# SMART3RGB.net
KiCad netlist of a schematic drawn in EAGLE
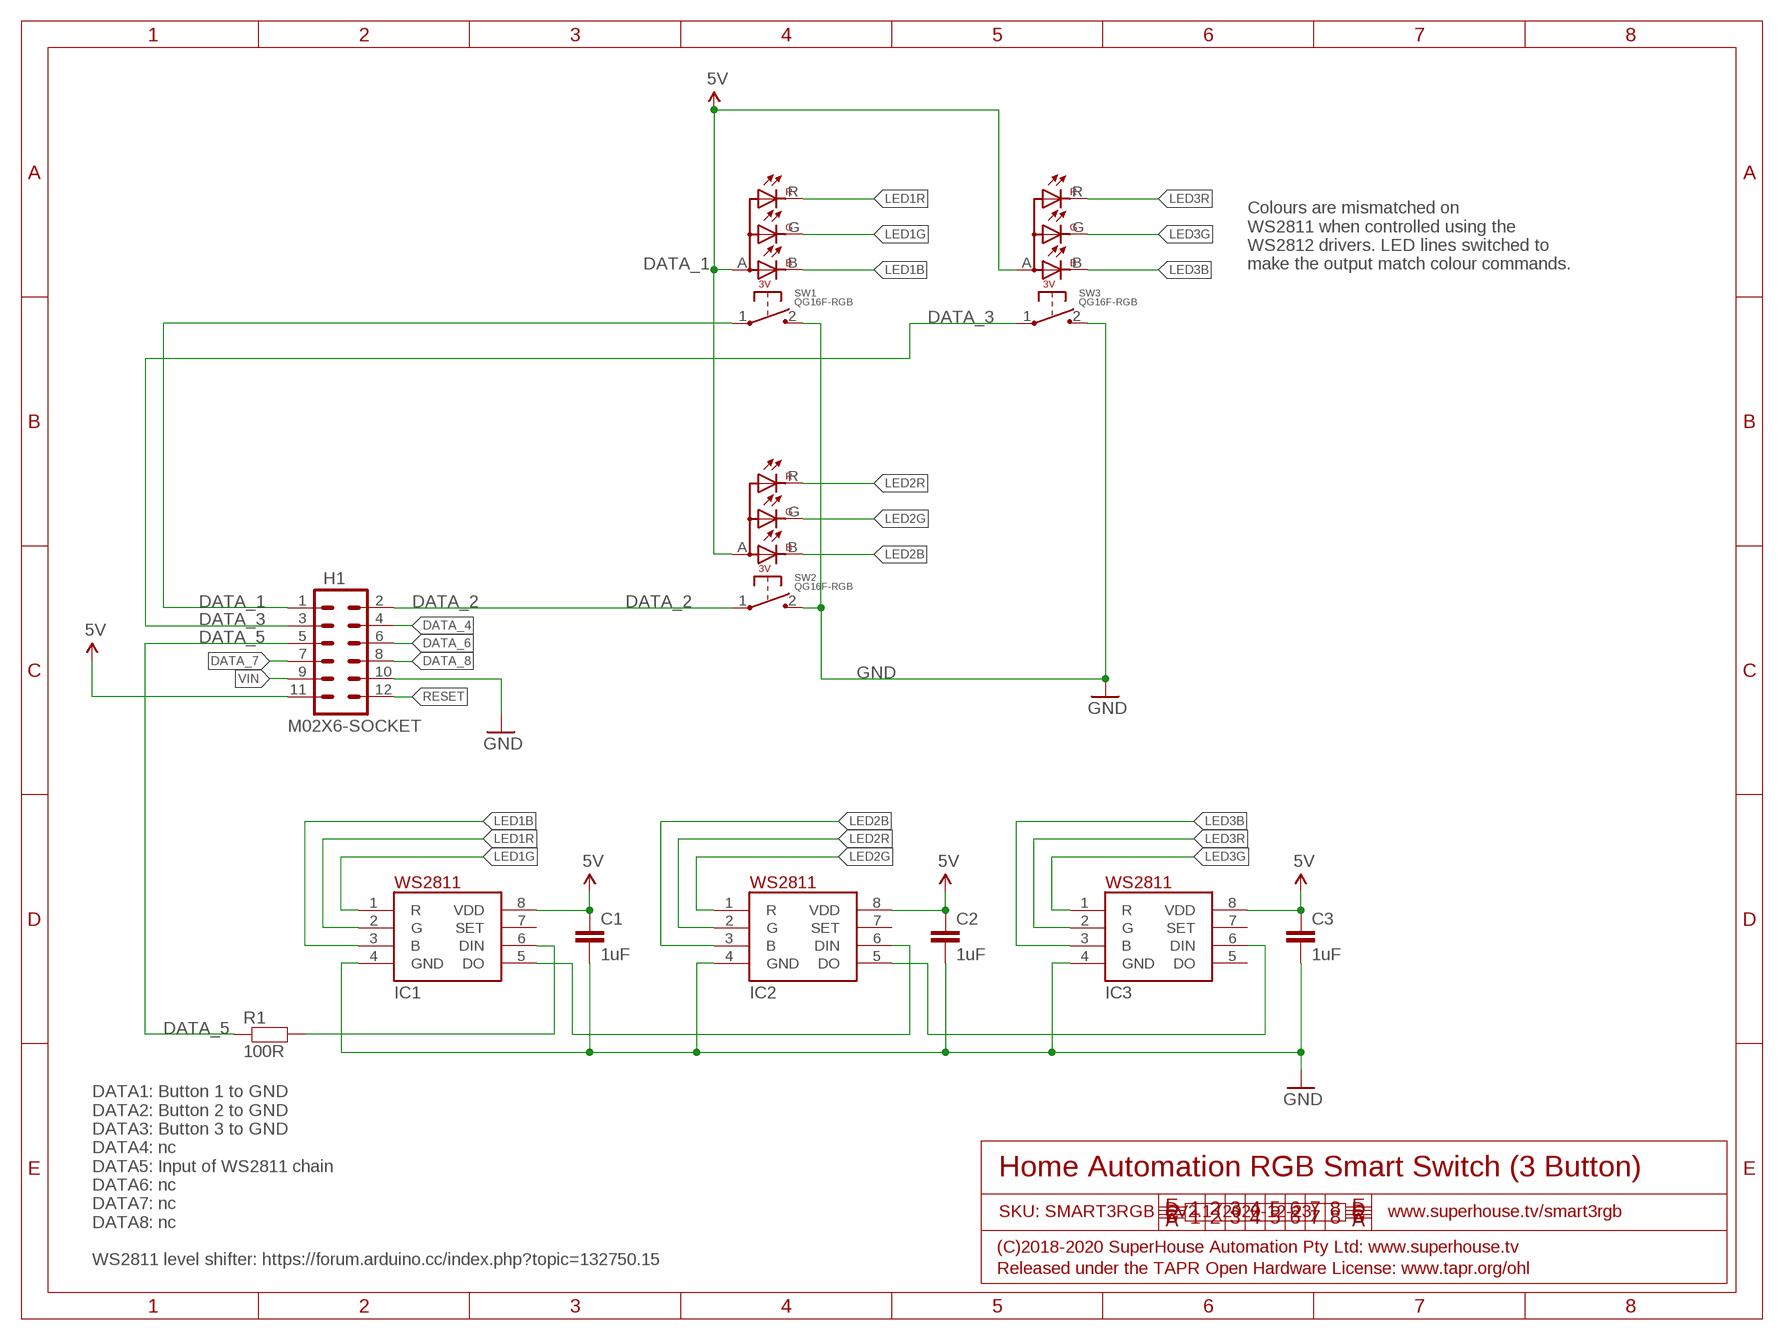
[diagram p0: schematic, sheet 1]

(export (version "E")
  (design (tool "Eeschema 10.0.6"))
  (components
    (comp (ref "C1")
      (value "1uF")
      (footprint "eagle-import:C0603")
      (libsource (lib "eagle-import") (part "CAP0603"))
    )
    (comp (ref "C2")
      (value "1uF")
      (footprint "eagle-import:C0603")
      (libsource (lib "eagle-import") (part "CAP0603"))
    )
    (comp (ref "C3")
      (value "1uF")
      (footprint "eagle-import:C0603")
      (libsource (lib "eagle-import") (part "CAP0603"))
    )
    (comp (ref "H1")
      (value "M02X6-SOCKET")
      (footprint "eagle-import:2X06-S")
      (libsource (lib "eagle-import") (part "M02X6-SOCKET"))
    )
    (comp (ref "IC1")
      (value "WS2811-SOP8")
      (footprint "eagle-import:SO08-SKINNYPADS")
      (libsource (lib "eagle-import") (part "WS2811-SOP8"))
    )
    (comp (ref "IC2")
      (value "WS2811-SOP8")
      (footprint "eagle-import:SO08-SKINNYPADS")
      (libsource (lib "eagle-import") (part "WS2811-SOP8"))
    )
    (comp (ref "IC3")
      (value "WS2811-SOP8")
      (footprint "eagle-import:SO08-SKINNYPADS")
      (libsource (lib "eagle-import") (part "WS2811-SOP8"))
    )
    (comp (ref "R1")
      (value "100R")
      (footprint "eagle-import:R0603")
      (libsource (lib "eagle-import") (part "RESISTOR0603"))
    )
    (comp (ref "SW1")
      (value "QG16F-RGB")
      (footprint "eagle-import:QG16F-RGB")
      (libsource (lib "eagle-import") (part "QG16F-RGB"))
    )
    (comp (ref "SW2")
      (value "QG16F-RGB")
      (footprint "eagle-import:QG16F-RGB")
      (libsource (lib "eagle-import") (part "QG16F-RGB"))
    )
    (comp (ref "SW3")
      (value "QG16F-RGB")
      (footprint "eagle-import:QG16F-RGB")
      (libsource (lib "eagle-import") (part "QG16F-RGB"))
    )
  )
  (nets
    (net (code "1") (name "/DATA_1") (class "Default")
      (node (ref "H1") (pin "1") (pinfunction "1_1") (pintype "passive"))
      (node (ref "SW1") (pin "1") (pinfunction "1_1") (pintype "passive"))
    )
    (net (code "2") (name "/DATA_2") (class "Default")
      (node (ref "H1") (pin "2") (pinfunction "2_2") (pintype "passive"))
      (node (ref "SW2") (pin "1") (pinfunction "1_1") (pintype "passive"))
    )
    (net (code "3") (name "/DATA_3") (class "Default")
      (node (ref "H1") (pin "3") (pinfunction "3_3") (pintype "passive"))
      (node (ref "SW3") (pin "1") (pinfunction "1_1") (pintype "passive"))
    )
    (net (code "4") (name "/DATA_5") (class "Default")
      (node (ref "H1") (pin "5") (pinfunction "5_5") (pintype "passive"))
      (node (ref "R1") (pin "1") (pinfunction "1_1") (pintype "passive"))
    )
    (net (code "5") (name "5V") (class "Default")
      (node (ref "C1") (pin "1") (pinfunction "1_1") (pintype "passive"))
      (node (ref "C2") (pin "1") (pinfunction "1_1") (pintype "passive"))
      (node (ref "C3") (pin "1") (pinfunction "1_1") (pintype "passive"))
      (node (ref "H1") (pin "11") (pinfunction "11_11") (pintype "passive"))
      (node (ref "IC1") (pin "8") (pinfunction "VDD_8") (pintype "power_in"))
      (node (ref "IC2") (pin "8") (pinfunction "VDD_8") (pintype "power_in"))
      (node (ref "IC3") (pin "8") (pinfunction "VDD_8") (pintype "power_in"))
      (node (ref "SW1") (pin "A") (pinfunction "+_A") (pintype "passive"))
      (node (ref "SW2") (pin "A") (pinfunction "+_A") (pintype "passive"))
      (node (ref "SW3") (pin "A") (pinfunction "+_A") (pintype "passive"))
    )
    (net (code "6") (name "DATA_4") (class "Default")
      (node (ref "H1") (pin "4") (pinfunction "4_4") (pintype "passive"))
    )
    (net (code "7") (name "DATA_6") (class "Default")
      (node (ref "H1") (pin "6") (pinfunction "6_6") (pintype "passive"))
    )
    (net (code "8") (name "DATA_7") (class "Default")
      (node (ref "H1") (pin "7") (pinfunction "7_7") (pintype "passive"))
    )
    (net (code "9") (name "DATA_8") (class "Default")
      (node (ref "H1") (pin "8") (pinfunction "8_8") (pintype "passive"))
    )
    (net (code "10") (name "GND") (class "Default")
      (node (ref "C1") (pin "2") (pinfunction "2_2") (pintype "passive"))
      (node (ref "C2") (pin "2") (pinfunction "2_2") (pintype "passive"))
      (node (ref "C3") (pin "2") (pinfunction "2_2") (pintype "passive"))
      (node (ref "H1") (pin "10") (pinfunction "10_10") (pintype "passive"))
      (node (ref "IC1") (pin "4") (pinfunction "GND_4") (pintype "power_in"))
      (node (ref "IC2") (pin "4") (pinfunction "GND_4") (pintype "power_in"))
      (node (ref "IC3") (pin "4") (pinfunction "GND_4") (pintype "power_in"))
      (node (ref "SW1") (pin "2") (pinfunction "2_2") (pintype "passive"))
      (node (ref "SW2") (pin "2") (pinfunction "2_2") (pintype "passive"))
      (node (ref "SW3") (pin "2") (pinfunction "2_2") (pintype "passive"))
    )
    (net (code "11") (name "LED1B") (class "Default")
      (node (ref "IC1") (pin "3") (pinfunction "B_3") (pintype "open_collector"))
      (node (ref "SW1") (pin "B") (pinfunction "B_B") (pintype "passive"))
    )
    (net (code "12") (name "LED1G") (class "Default")
      (node (ref "IC1") (pin "1") (pinfunction "R_1") (pintype "open_collector"))
      (node (ref "SW1") (pin "G") (pinfunction "G_G") (pintype "passive"))
    )
    (net (code "13") (name "LED1R") (class "Default")
      (node (ref "IC1") (pin "2") (pinfunction "G_2") (pintype "open_collector"))
      (node (ref "SW1") (pin "R") (pinfunction "R_R") (pintype "passive"))
    )
    (net (code "14") (name "LED2B") (class "Default")
      (node (ref "IC2") (pin "3") (pinfunction "B_3") (pintype "open_collector"))
      (node (ref "SW2") (pin "B") (pinfunction "B_B") (pintype "passive"))
    )
    (net (code "15") (name "LED2G") (class "Default")
      (node (ref "IC2") (pin "1") (pinfunction "R_1") (pintype "open_collector"))
      (node (ref "SW2") (pin "G") (pinfunction "G_G") (pintype "passive"))
    )
    (net (code "16") (name "LED2R") (class "Default")
      (node (ref "IC2") (pin "2") (pinfunction "G_2") (pintype "open_collector"))
      (node (ref "SW2") (pin "R") (pinfunction "R_R") (pintype "passive"))
    )
    (net (code "17") (name "LED3B") (class "Default")
      (node (ref "IC3") (pin "3") (pinfunction "B_3") (pintype "open_collector"))
      (node (ref "SW3") (pin "B") (pinfunction "B_B") (pintype "passive"))
    )
    (net (code "18") (name "LED3G") (class "Default")
      (node (ref "IC3") (pin "1") (pinfunction "R_1") (pintype "open_collector"))
      (node (ref "SW3") (pin "G") (pinfunction "G_G") (pintype "passive"))
    )
    (net (code "19") (name "LED3R") (class "Default")
      (node (ref "IC3") (pin "2") (pinfunction "G_2") (pintype "open_collector"))
      (node (ref "SW3") (pin "R") (pinfunction "R_R") (pintype "passive"))
    )
    (net (code "20") (name "Net-(IC1-DIN)") (class "Default")
      (node (ref "IC1") (pin "6") (pinfunction "DIN_6") (pintype "input"))
      (node (ref "R1") (pin "2") (pinfunction "2_2") (pintype "passive"))
    )
    (net (code "21") (name "Net-(IC1-DO)") (class "Default")
      (node (ref "IC1") (pin "5") (pinfunction "DO_5") (pintype "output"))
      (node (ref "IC2") (pin "6") (pinfunction "DIN_6") (pintype "input"))
    )
    (net (code "22") (name "Net-(IC2-DO)") (class "Default")
      (node (ref "IC2") (pin "5") (pinfunction "DO_5") (pintype "output"))
      (node (ref "IC3") (pin "6") (pinfunction "DIN_6") (pintype "input"))
    )
    (net (code "23") (name "RESET") (class "Default")
      (node (ref "H1") (pin "12") (pinfunction "12_12") (pintype "passive"))
    )
    (net (code "24") (name "VIN") (class "Default")
      (node (ref "H1") (pin "9") (pinfunction "9_9") (pintype "passive"))
    )
    (net (code "25") (name "unconnected-(IC1-SET-Pad7)") (class "Default")
      (node (ref "IC1") (pin "7") (pinfunction "SET_7") (pintype "input"))
    )
    (net (code "26") (name "unconnected-(IC2-SET-Pad7)") (class "Default")
      (node (ref "IC2") (pin "7") (pinfunction "SET_7") (pintype "input"))
    )
    (net (code "27") (name "unconnected-(IC3-DO-Pad5)") (class "Default")
      (node (ref "IC3") (pin "5") (pinfunction "DO_5") (pintype "output"))
    )
    (net (code "28") (name "unconnected-(IC3-SET-Pad7)") (class "Default")
      (node (ref "IC3") (pin "7") (pinfunction "SET_7") (pintype "input"))
    )
  )
)
